# PowerSupply_12V_v2.net
KiCad netlist of a schematic drawn in EAGLE
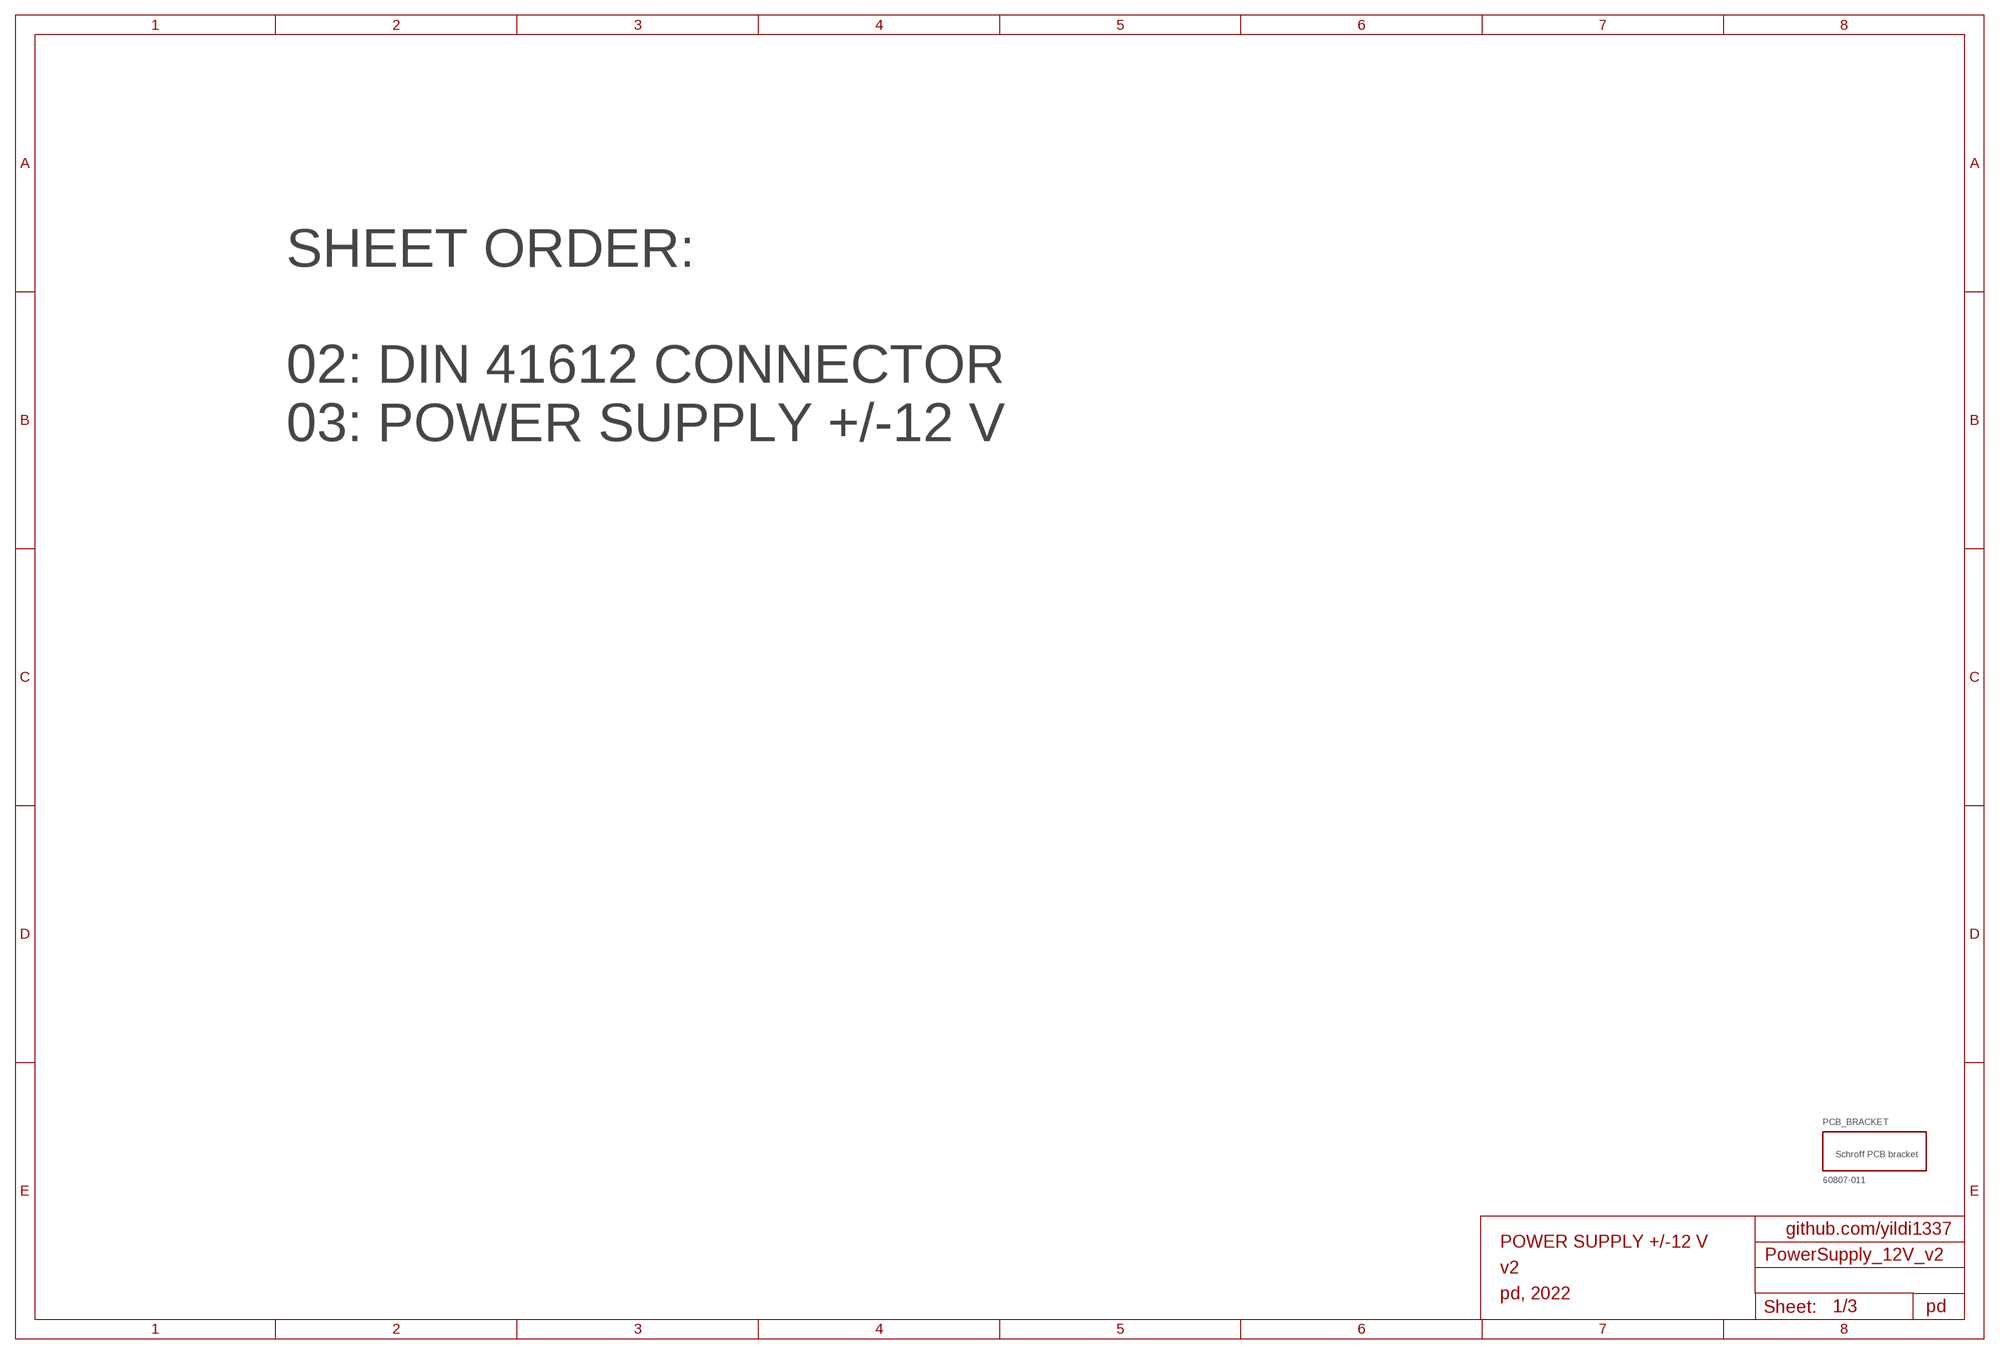
[diagram p0: schematic, sheet 1]
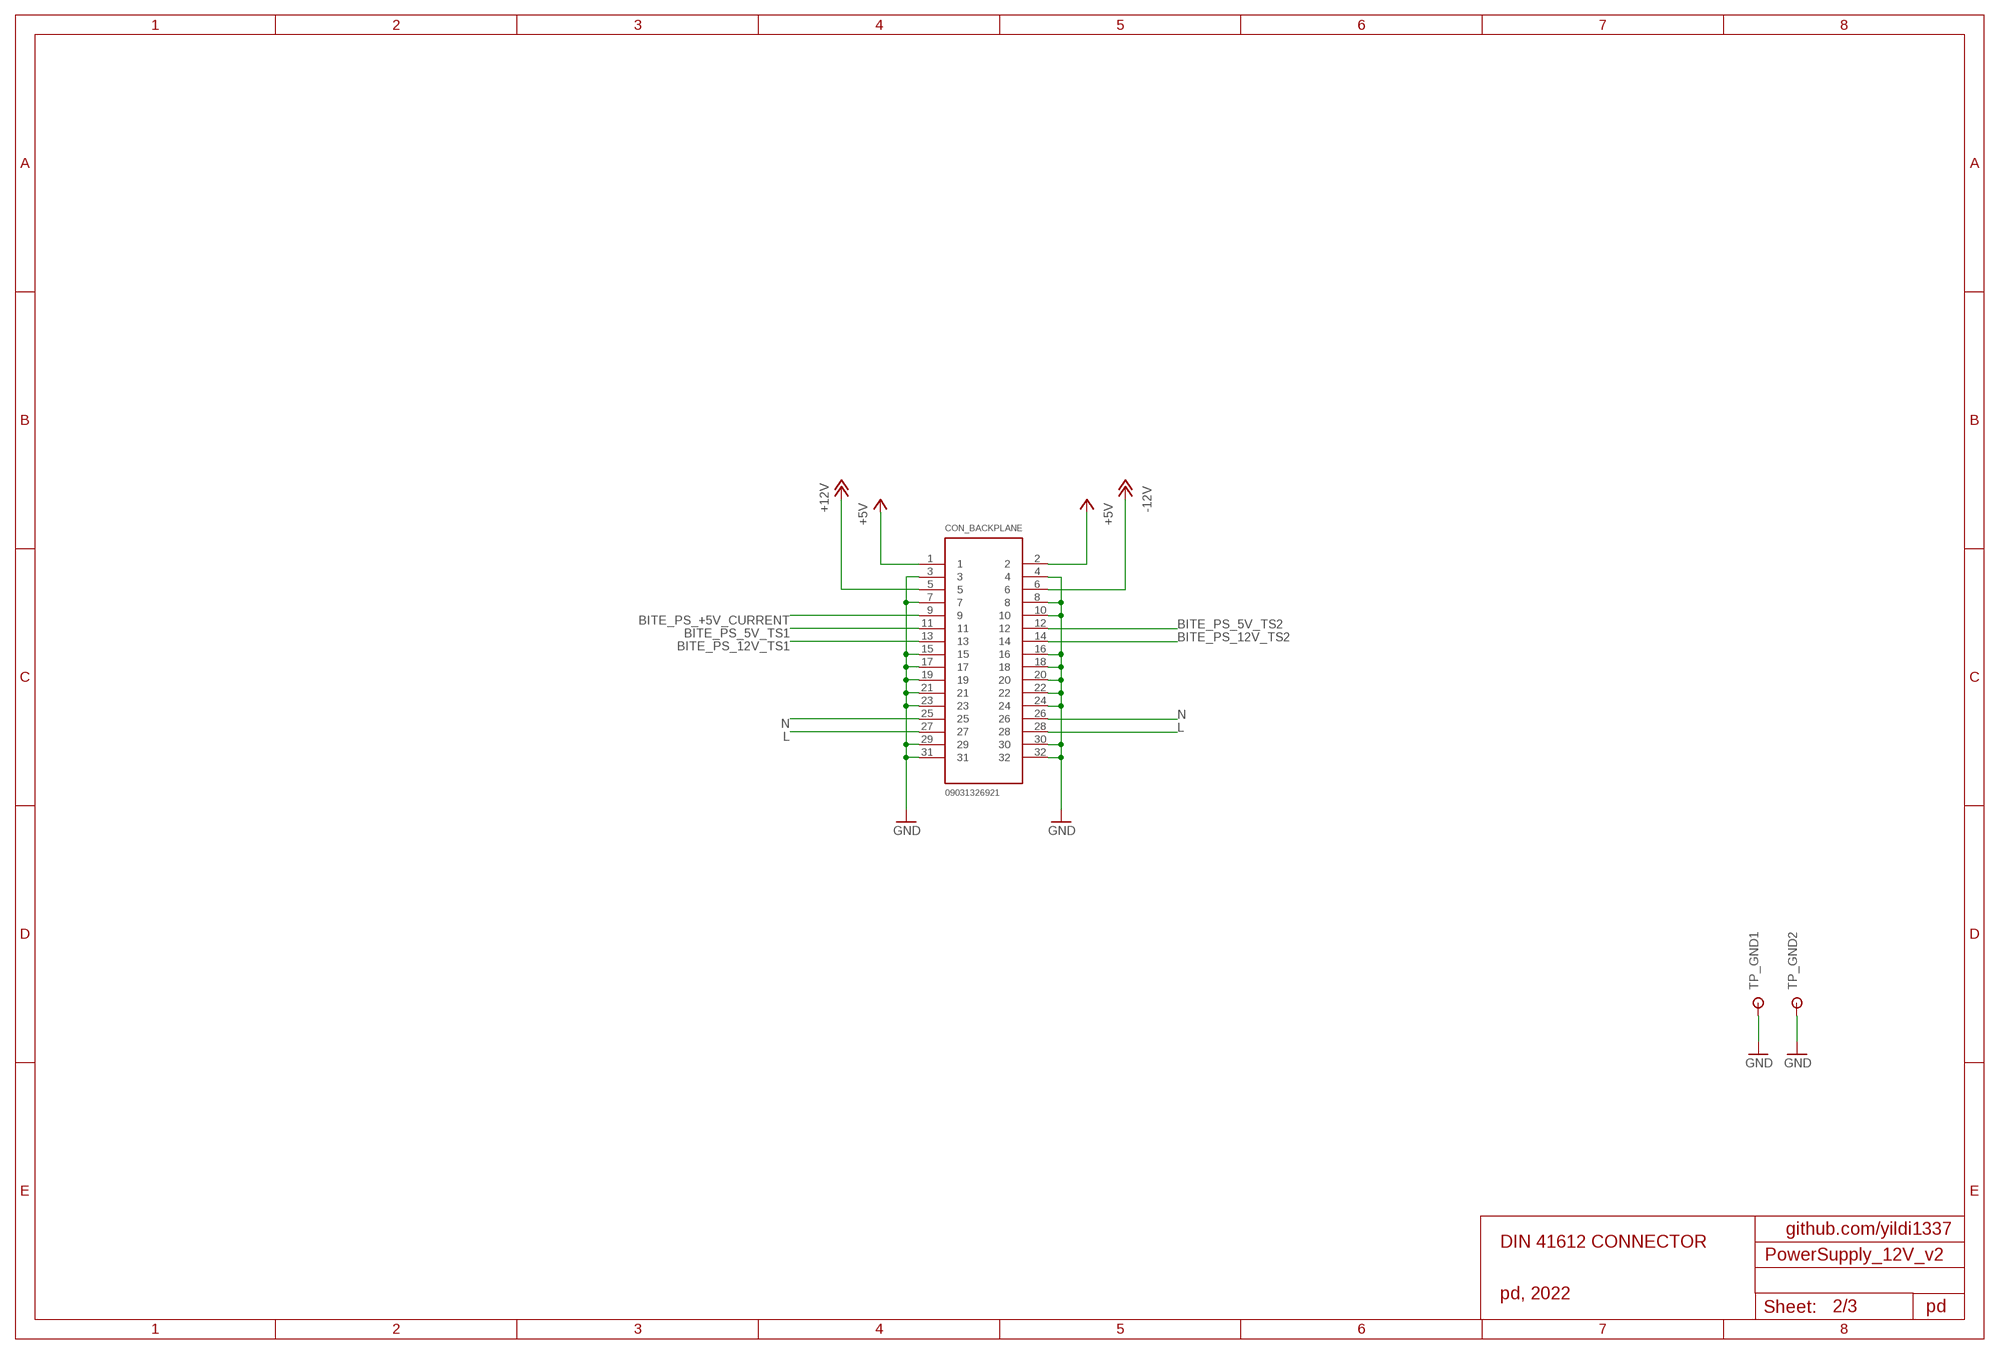
[diagram p1: schematic, sheet 2]
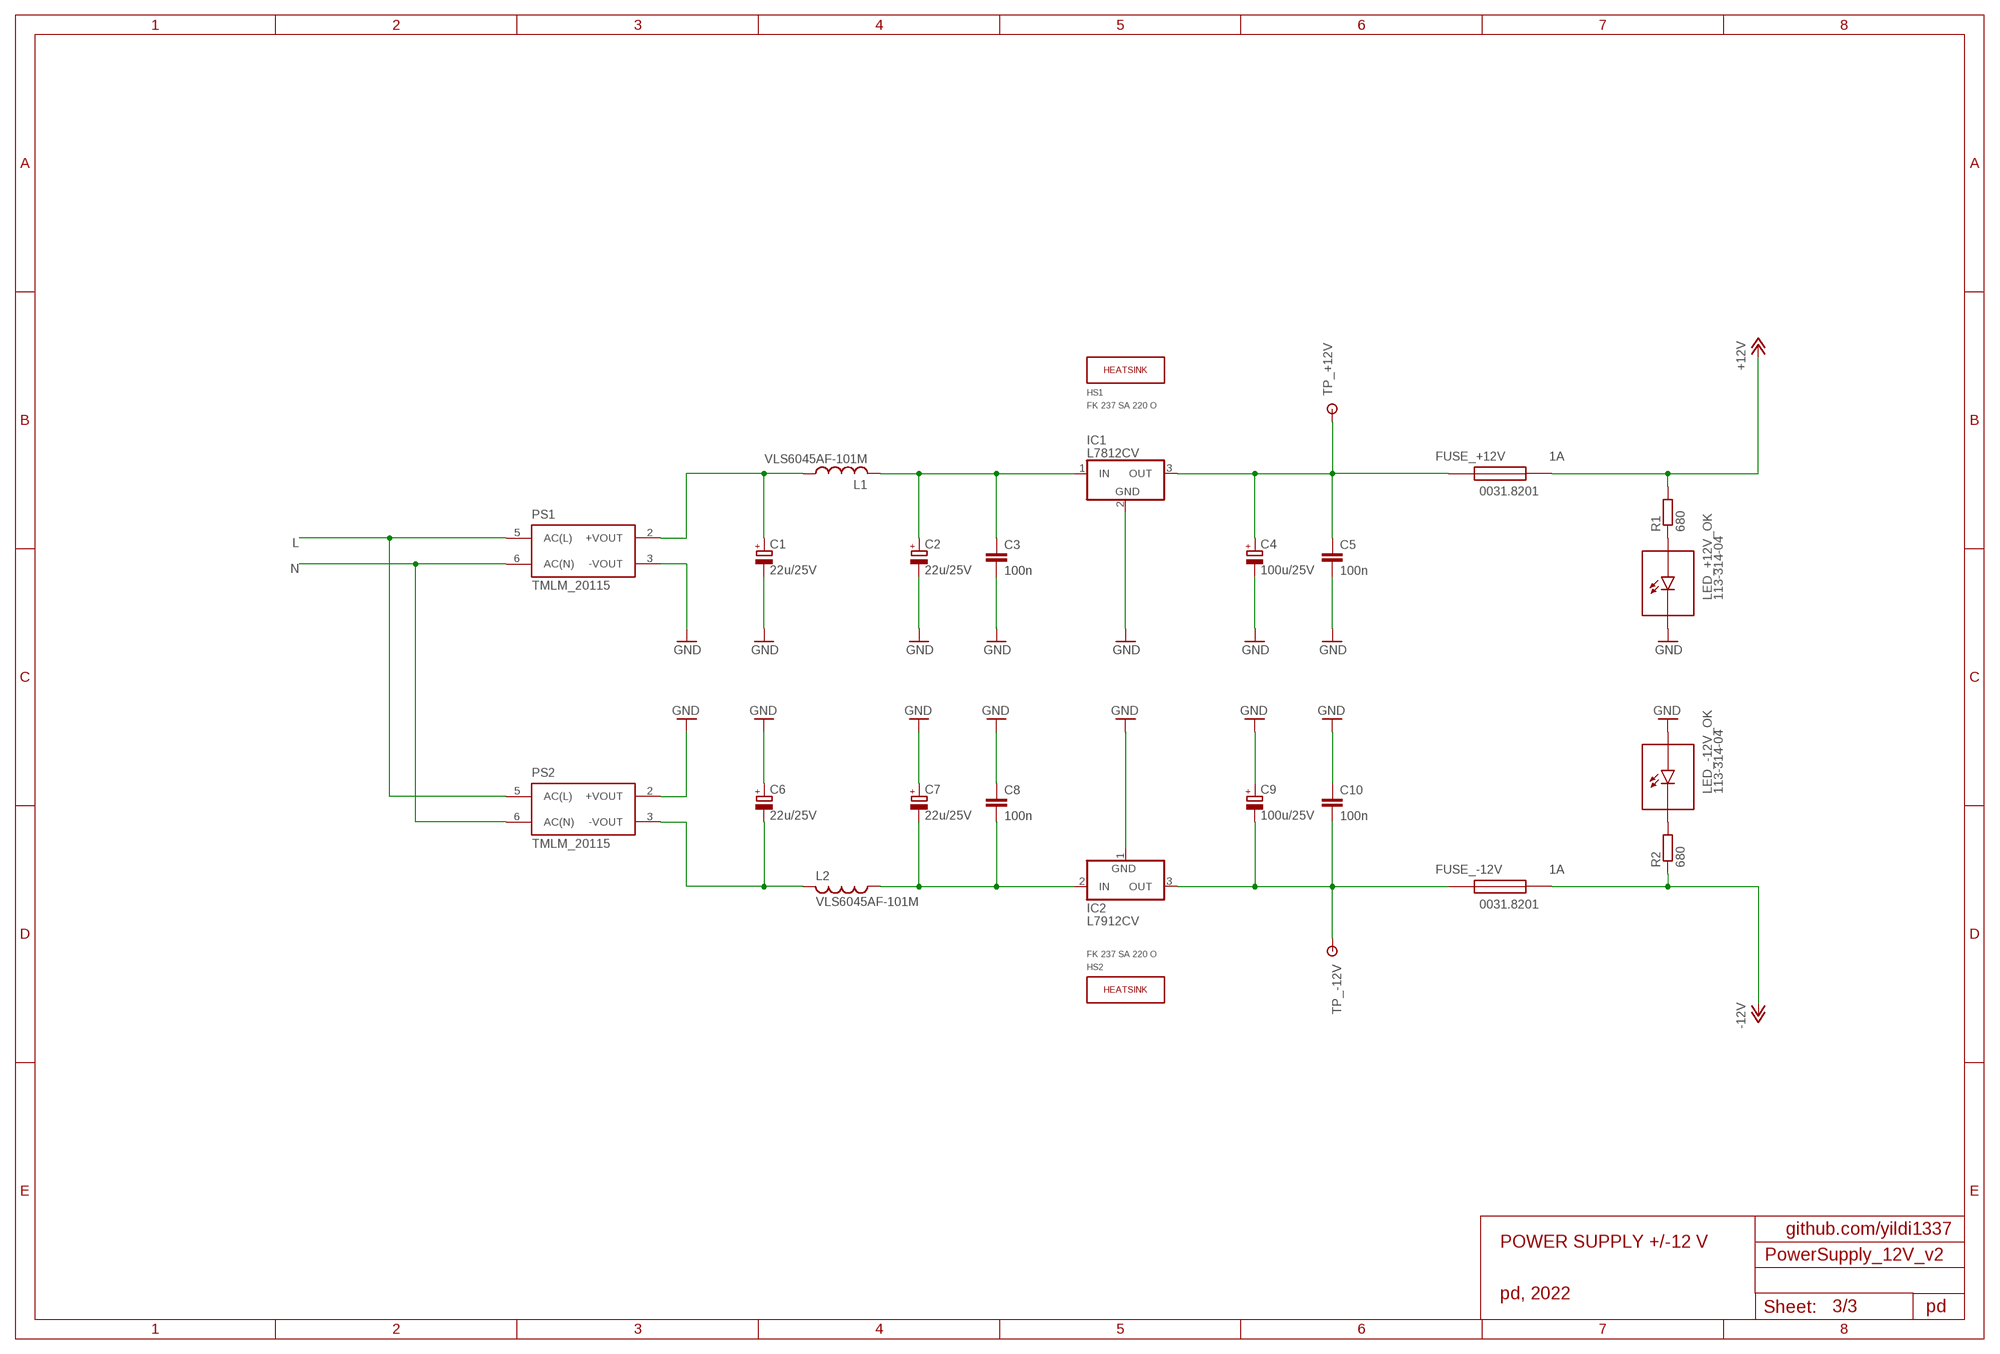
[diagram p2: schematic, sheet 3]

(export (version "E")
  (design (tool "Eeschema 10.0.6"))
  (components
    (comp (ref "PCB_BRACKET")
      (value "60807-011")
      (footprint "eagle-import:60807-011")
      (libsource (lib "eagle-import") (part "60807-011"))
    )
    (comp (ref "C1")
      (value "22u/25V")
      (footprint "eagle-import:153CLV-0505")
      (libsource (lib "eagle-import") (part "CPOL-EU153CLV-0505"))
    )
    (comp (ref "C2")
      (value "22u/25V")
      (footprint "eagle-import:153CLV-0505")
      (libsource (lib "eagle-import") (part "CPOL-EU153CLV-0505"))
    )
    (comp (ref "C3")
      (value "100n")
      (footprint "eagle-import:C0603")
      (libsource (lib "eagle-import") (part "C-EUC0603"))
    )
    (comp (ref "C4")
      (value "100u/25V")
      (footprint "eagle-import:153CLV-0810")
      (libsource (lib "eagle-import") (part "CPOL-EU153CLV-0810"))
    )
    (comp (ref "C5")
      (value "100n")
      (footprint "eagle-import:C0603")
      (libsource (lib "eagle-import") (part "C-EUC0603"))
    )
    (comp (ref "C6")
      (value "22u/25V")
      (footprint "eagle-import:153CLV-0505")
      (libsource (lib "eagle-import") (part "CPOL-EU153CLV-0505"))
    )
    (comp (ref "C7")
      (value "22u/25V")
      (footprint "eagle-import:153CLV-0505")
      (libsource (lib "eagle-import") (part "CPOL-EU153CLV-0505"))
    )
    (comp (ref "C8")
      (value "100n")
      (footprint "eagle-import:C0603")
      (libsource (lib "eagle-import") (part "C-EUC0603"))
    )
    (comp (ref "C9")
      (value "100u/25V")
      (footprint "eagle-import:153CLV-0810")
      (libsource (lib "eagle-import") (part "CPOL-EU153CLV-0810"))
    )
    (comp (ref "C10")
      (value "100n")
      (footprint "eagle-import:C0603")
      (libsource (lib "eagle-import") (part "C-EUC0603"))
    )
    (comp (ref "FUSE_+12V")
      (value "0031.8201")
      (footprint "eagle-import:0031.8201")
      (libsource (lib "eagle-import") (part "0031.8201"))
    )
    (comp (ref "FUSE_-12V")
      (value "0031.8201")
      (footprint "eagle-import:0031.8201")
      (libsource (lib "eagle-import") (part "0031.8201"))
    )
    (comp (ref "HS1")
      (value "FK 237 SA 220 O")
      (footprint "eagle-import:FK_237_SA_220_O")
      (libsource (lib "eagle-import") (part "FK_237_SA_220_O"))
    )
    (comp (ref "HS2")
      (value "FK 237 SA 220 O")
      (footprint "eagle-import:FK_237_SA_220_O")
      (libsource (lib "eagle-import") (part "FK_237_SA_220_O"))
    )
    (comp (ref "IC1")
      (value "L7812CV")
      (footprint "eagle-import:L7812CV")
      (libsource (lib "eagle-import") (part "L7812CV"))
    )
    (comp (ref "IC2")
      (value "L7912CV")
      (footprint "eagle-import:L7912CV")
      (libsource (lib "eagle-import") (part "L7912CV"))
    )
    (comp (ref "L1")
      (value "VLS6045AF-101M")
      (footprint "eagle-import:VLS6045AF-101M")
      (libsource (lib "eagle-import") (part "VLS6045AF-101M"))
    )
    (comp (ref "L2")
      (value "VLS6045AF-101M")
      (footprint "eagle-import:VLS6045AF-101M")
      (libsource (lib "eagle-import") (part "VLS6045AF-101M"))
    )
    (comp (ref "LED_+12V_OK")
      (value "113-314-04")
      (footprint "eagle-import:113-314-04")
      (libsource (lib "eagle-import") (part "113-314-04"))
    )
    (comp (ref "LED_-12V_OK")
      (value "113-314-04")
      (footprint "eagle-import:113-314-04")
      (libsource (lib "eagle-import") (part "113-314-04"))
    )
    (comp (ref "PS1")
      (value "TMLM_20115")
      (footprint "eagle-import:TMLM_201XX")
      (libsource (lib "eagle-import") (part "TMLM_201XX"))
    )
    (comp (ref "PS2")
      (value "TMLM_20115")
      (footprint "eagle-import:TMLM_201XX")
      (libsource (lib "eagle-import") (part "TMLM_201XX"))
    )
    (comp (ref "R1")
      (value "680")
      (footprint "eagle-import:R0603")
      (libsource (lib "eagle-import") (part "R-EU_R0603"))
    )
    (comp (ref "R2")
      (value "680")
      (footprint "eagle-import:R0603")
      (libsource (lib "eagle-import") (part "R-EU_R0603"))
    )
    (comp (ref "TP_+12V")
      (value "RSPRO-1MM-TERMINAL-POST-2622034")
      (footprint "eagle-import:RSPRO-1MM-TERMINAL-POST-2622034")
      (libsource (lib "eagle-import") (part "RSPRO-1MM-TERMINAL-POST-2622034"))
    )
    (comp (ref "TP_-12V")
      (value "RSPRO-1MM-TERMINAL-POST-2622034")
      (footprint "eagle-import:RSPRO-1MM-TERMINAL-POST-2622034")
      (libsource (lib "eagle-import") (part "RSPRO-1MM-TERMINAL-POST-2622034"))
    )
    (comp (ref "CON_BACKPLANE")
      (value "09031326921")
      (footprint "eagle-import:09031326921")
      (libsource (lib "eagle-import") (part "09031326921"))
    )
    (comp (ref "TP_GND1")
      (value "RSPRO-1MM-TERMINAL-POST-2622034")
      (footprint "eagle-import:RSPRO-1MM-TERMINAL-POST-2622034")
      (libsource (lib "eagle-import") (part "RSPRO-1MM-TERMINAL-POST-2622034"))
    )
    (comp (ref "TP_GND2")
      (value "RSPRO-1MM-TERMINAL-POST-2622034")
      (footprint "eagle-import:RSPRO-1MM-TERMINAL-POST-2622034")
      (libsource (lib "eagle-import") (part "RSPRO-1MM-TERMINAL-POST-2622034"))
    )
  )
  (nets
    (net (code "1") (name "+5V") (class "Default")
      (node (ref "CON_BACKPLANE") (pin "1") (pinfunction "1_1") (pintype "bidirectional"))
      (node (ref "CON_BACKPLANE") (pin "2") (pinfunction "2_2") (pintype "bidirectional"))
    )
    (net (code "2") (name "+12V") (class "Default")
      (node (ref "CON_BACKPLANE") (pin "5") (pinfunction "5_5") (pintype "bidirectional"))
      (node (ref "FUSE_+12V") (pin "2") (pinfunction "P$2_2") (pintype "bidirectional"))
      (node (ref "R1") (pin "2") (pinfunction "2_2") (pintype "passive"))
    )
    (net (code "3") (name "-12V") (class "Default")
      (node (ref "CON_BACKPLANE") (pin "6") (pinfunction "6_6") (pintype "bidirectional"))
      (node (ref "FUSE_-12V") (pin "2") (pinfunction "P$2_2") (pintype "bidirectional"))
      (node (ref "R2") (pin "1") (pinfunction "1_1") (pintype "passive"))
    )
    (net (code "4") (name "BITE_PS_+5V_CURRENT") (class "Default")
      (node (ref "CON_BACKPLANE") (pin "9") (pinfunction "9_9") (pintype "bidirectional"))
    )
    (net (code "5") (name "BITE_PS_5V_TS1") (class "Default")
      (node (ref "CON_BACKPLANE") (pin "11") (pinfunction "11_11") (pintype "bidirectional"))
    )
    (net (code "6") (name "BITE_PS_5V_TS2") (class "Default")
      (node (ref "CON_BACKPLANE") (pin "12") (pinfunction "12_12") (pintype "bidirectional"))
    )
    (net (code "7") (name "BITE_PS_12V_TS1") (class "Default")
      (node (ref "CON_BACKPLANE") (pin "13") (pinfunction "13_13") (pintype "bidirectional"))
    )
    (net (code "8") (name "BITE_PS_12V_TS2") (class "Default")
      (node (ref "CON_BACKPLANE") (pin "14") (pinfunction "14_14") (pintype "bidirectional"))
    )
    (net (code "9") (name "GND") (class "Default")
      (node (ref "C1") (pin "-") (pinfunction "-_-") (pintype "passive"))
      (node (ref "C10") (pin "1") (pinfunction "1_1") (pintype "passive"))
      (node (ref "C2") (pin "-") (pinfunction "-_-") (pintype "passive"))
      (node (ref "C3") (pin "2") (pinfunction "2_2") (pintype "passive"))
      (node (ref "C4") (pin "-") (pinfunction "-_-") (pintype "passive"))
      (node (ref "C5") (pin "2") (pinfunction "2_2") (pintype "passive"))
      (node (ref "C6") (pin "+") (pinfunction "+_+") (pintype "passive"))
      (node (ref "C7") (pin "+") (pinfunction "+_+") (pintype "passive"))
      (node (ref "C8") (pin "1") (pinfunction "1_1") (pintype "passive"))
      (node (ref "C9") (pin "+") (pinfunction "+_+") (pintype "passive"))
      (node (ref "CON_BACKPLANE") (pin "10") (pinfunction "10_10") (pintype "bidirectional"))
      (node (ref "CON_BACKPLANE") (pin "15") (pinfunction "15_15") (pintype "bidirectional"))
      (node (ref "CON_BACKPLANE") (pin "16") (pinfunction "16_16") (pintype "bidirectional"))
      (node (ref "CON_BACKPLANE") (pin "17") (pinfunction "17_17") (pintype "bidirectional"))
      (node (ref "CON_BACKPLANE") (pin "18") (pinfunction "18_18") (pintype "bidirectional"))
      (node (ref "CON_BACKPLANE") (pin "19") (pinfunction "19_19") (pintype "bidirectional"))
      (node (ref "CON_BACKPLANE") (pin "20") (pinfunction "20_20") (pintype "bidirectional"))
      (node (ref "CON_BACKPLANE") (pin "21") (pinfunction "21_21") (pintype "bidirectional"))
      (node (ref "CON_BACKPLANE") (pin "22") (pinfunction "22_22") (pintype "bidirectional"))
      (node (ref "CON_BACKPLANE") (pin "23") (pinfunction "23_23") (pintype "bidirectional"))
      (node (ref "CON_BACKPLANE") (pin "24") (pinfunction "24_24") (pintype "bidirectional"))
      (node (ref "CON_BACKPLANE") (pin "29") (pinfunction "29_29") (pintype "bidirectional"))
      (node (ref "CON_BACKPLANE") (pin "3") (pinfunction "3_3") (pintype "bidirectional"))
      (node (ref "CON_BACKPLANE") (pin "30") (pinfunction "30_30") (pintype "bidirectional"))
      (node (ref "CON_BACKPLANE") (pin "31") (pinfunction "31_31") (pintype "bidirectional"))
      (node (ref "CON_BACKPLANE") (pin "32") (pinfunction "32_32") (pintype "bidirectional"))
      (node (ref "CON_BACKPLANE") (pin "4") (pinfunction "4_4") (pintype "bidirectional"))
      (node (ref "CON_BACKPLANE") (pin "7") (pinfunction "7_7") (pintype "bidirectional"))
      (node (ref "CON_BACKPLANE") (pin "8") (pinfunction "8_8") (pintype "bidirectional"))
      (node (ref "IC1") (pin "2") (pinfunction "GND_2") (pintype "passive"))
      (node (ref "IC2") (pin "1") (pinfunction "GND_1") (pintype "passive"))
      (node (ref "LED_+12V_OK") (pin "-") (pinfunction "C_-") (pintype "passive"))
      (node (ref "LED_-12V_OK") (pin "+") (pinfunction "A_+") (pintype "passive"))
      (node (ref "PS1") (pin "3") (pinfunction "-VOUT_3") (pintype "output"))
      (node (ref "PS2") (pin "2") (pinfunction "+VOUT_2") (pintype "output"))
      (node (ref "TP_GND1") (pin "P$1") (pinfunction "P$1_P$1") (pintype "bidirectional"))
      (node (ref "TP_GND2") (pin "P$1") (pinfunction "P$1_P$1") (pintype "bidirectional"))
    )
    (net (code "10") (name "L") (class "Default")
      (node (ref "CON_BACKPLANE") (pin "27") (pinfunction "27_27") (pintype "bidirectional"))
      (node (ref "CON_BACKPLANE") (pin "28") (pinfunction "28_28") (pintype "bidirectional"))
      (node (ref "PS1") (pin "5") (pinfunction "AC(L)_5") (pintype "input"))
      (node (ref "PS2") (pin "5") (pinfunction "AC(L)_5") (pintype "input"))
    )
    (net (code "11") (name "N") (class "Default")
      (node (ref "CON_BACKPLANE") (pin "25") (pinfunction "25_25") (pintype "bidirectional"))
      (node (ref "CON_BACKPLANE") (pin "26") (pinfunction "26_26") (pintype "bidirectional"))
      (node (ref "PS1") (pin "6") (pinfunction "AC(N)_6") (pintype "input"))
      (node (ref "PS2") (pin "6") (pinfunction "AC(N)_6") (pintype "input"))
    )
    (net (code "12") (name "Net-(FUSE_+12V-P$1)") (class "Default")
      (node (ref "C4") (pin "+") (pinfunction "+_+") (pintype "passive"))
      (node (ref "C5") (pin "1") (pinfunction "1_1") (pintype "passive"))
      (node (ref "FUSE_+12V") (pin "1") (pinfunction "P$1_1") (pintype "bidirectional"))
      (node (ref "IC1") (pin "3") (pinfunction "OUT_3") (pintype "passive"))
      (node (ref "TP_+12V") (pin "P$1") (pinfunction "P$1_P$1") (pintype "bidirectional"))
    )
    (net (code "13") (name "Net-(FUSE_-12V-P$1)") (class "Default")
      (node (ref "C10") (pin "2") (pinfunction "2_2") (pintype "passive"))
      (node (ref "C9") (pin "-") (pinfunction "-_-") (pintype "passive"))
      (node (ref "FUSE_-12V") (pin "1") (pinfunction "P$1_1") (pintype "bidirectional"))
      (node (ref "IC2") (pin "3") (pinfunction "OUT_3") (pintype "passive"))
      (node (ref "TP_-12V") (pin "P$1") (pinfunction "P$1_P$1") (pintype "bidirectional"))
    )
    (net (code "14") (name "Net-(IC1-IN)") (class "Default")
      (node (ref "C2") (pin "+") (pinfunction "+_+") (pintype "passive"))
      (node (ref "C3") (pin "1") (pinfunction "1_1") (pintype "passive"))
      (node (ref "IC1") (pin "1") (pinfunction "IN_1") (pintype "input"))
      (node (ref "L1") (pin "2") (pinfunction "2_2") (pintype "passive"))
    )
    (net (code "15") (name "Net-(IC2-IN)") (class "Default")
      (node (ref "C7") (pin "-") (pinfunction "-_-") (pintype "passive"))
      (node (ref "C8") (pin "2") (pinfunction "2_2") (pintype "passive"))
      (node (ref "IC2") (pin "2") (pinfunction "IN_2") (pintype "input"))
      (node (ref "L2") (pin "1") (pinfunction "1_1") (pintype "passive"))
    )
    (net (code "16") (name "Net-(LED_+12V_OK-A)") (class "Default")
      (node (ref "LED_+12V_OK") (pin "+") (pinfunction "A_+") (pintype "passive"))
      (node (ref "R1") (pin "1") (pinfunction "1_1") (pintype "passive"))
    )
    (net (code "17") (name "Net-(LED_-12V_OK-C)") (class "Default")
      (node (ref "LED_-12V_OK") (pin "-") (pinfunction "C_-") (pintype "passive"))
      (node (ref "R2") (pin "2") (pinfunction "2_2") (pintype "passive"))
    )
    (net (code "18") (name "Net-(PS1-+VOUT)") (class "Default")
      (node (ref "C1") (pin "+") (pinfunction "+_+") (pintype "passive"))
      (node (ref "L1") (pin "1") (pinfunction "1_1") (pintype "passive"))
      (node (ref "PS1") (pin "2") (pinfunction "+VOUT_2") (pintype "output"))
    )
    (net (code "19") (name "Net-(PS2--VOUT)") (class "Default")
      (node (ref "C6") (pin "-") (pinfunction "-_-") (pintype "passive"))
      (node (ref "L2") (pin "2") (pinfunction "2_2") (pintype "passive"))
      (node (ref "PS2") (pin "3") (pinfunction "-VOUT_3") (pintype "output"))
    )
  )
)
